# main.net
KiCad netlist of a schematic drawn in EAGLE
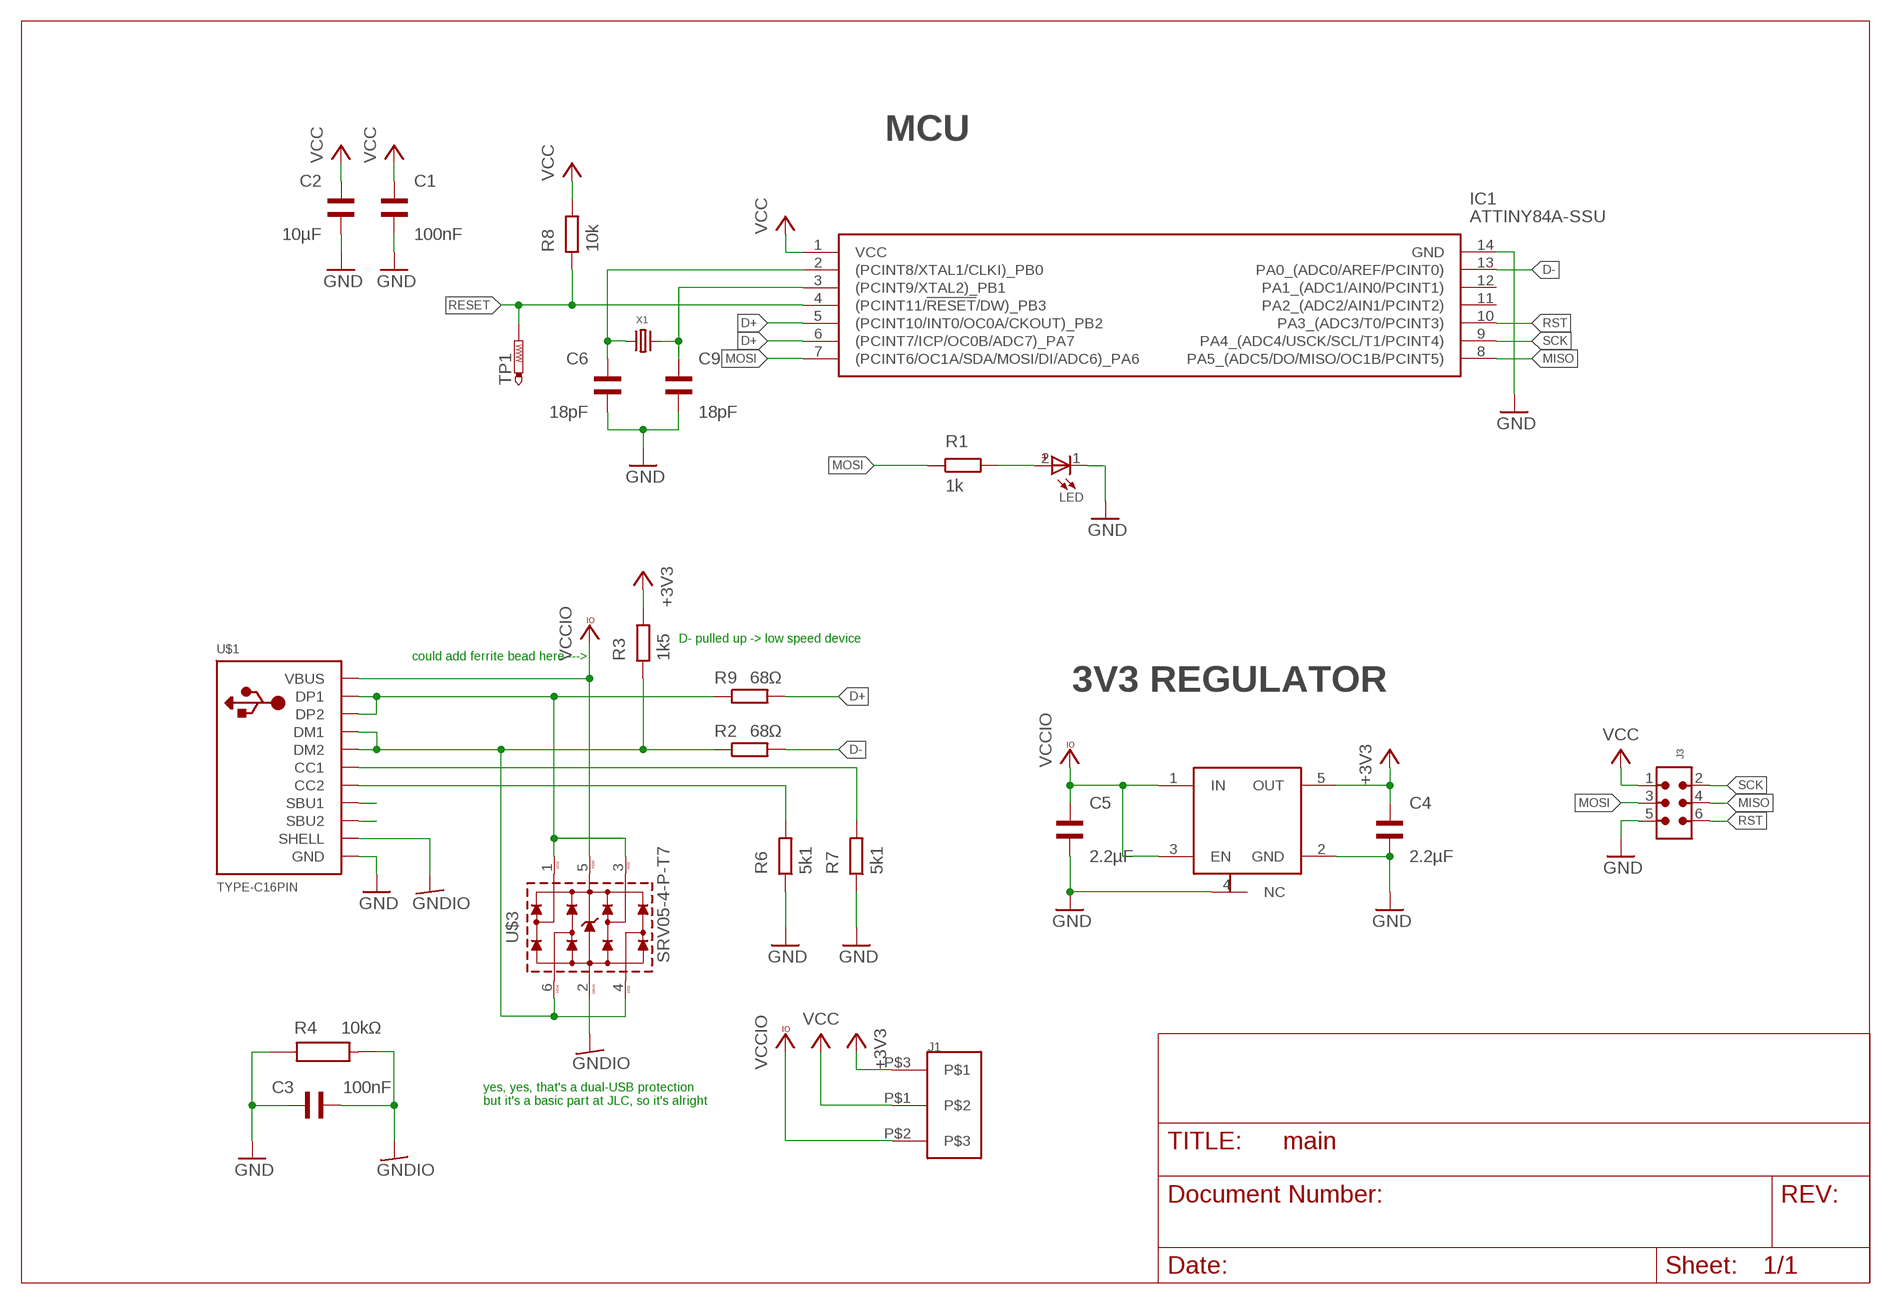
[diagram p0: schematic, sheet 1]

(export (version "E")
  (design (tool "Eeschema 10.0.6"))
  (components
    (comp (ref "C1")
      (value "100nF")
      (footprint "eagle-import:WCAP-CSGP_0603_REFLOW")
      (libsource (lib "eagle-import") (part "WCAP-CSGP_0603_REFLOW_885012206046"))
    )
    (comp (ref "C2")
      (value "10µF")
      (footprint "eagle-import:WCAP-CSGP_0603_REFLOW")
      (libsource (lib "eagle-import") (part "WCAP-CSGP_0603_REFLOW_885012106012"))
    )
    (comp (ref "C3")
      (value "100nF")
      (footprint "eagle-import:WCAP-CSGP_0603_REFLOW")
      (libsource (lib "eagle-import") (part "WCAP-CSGP_0603_REFLOW_885012206046"))
    )
    (comp (ref "C4")
      (value "2.2µF")
      (footprint "eagle-import:WCAP-CSGP_0603_REFLOW")
      (libsource (lib "eagle-import") (part "WCAP-CSGP_0603_REFLOW_885012206027"))
    )
    (comp (ref "C5")
      (value "2.2µF")
      (footprint "eagle-import:WCAP-CSGP_0603_REFLOW")
      (libsource (lib "eagle-import") (part "WCAP-CSGP_0603_REFLOW_885012206027"))
    )
    (comp (ref "C6")
      (value "18pF")
      (footprint "eagle-import:WCAP-CSGP_0603_REFLOW")
      (libsource (lib "eagle-import") (part "WCAP-CSGP_0603_REFLOW_885012206046"))
    )
    (comp (ref "C9")
      (value "18pF")
      (footprint "eagle-import:WCAP-CSGP_0603_REFLOW")
      (libsource (lib "eagle-import") (part "WCAP-CSGP_0603_REFLOW_885012206046"))
    )
    (comp (ref "IC1")
      (value "ATTINY84A-SSU")
      (footprint "eagle-import:SOIC127P600X175-14N")
      (fields (field (name "MOUSER_PART_NUMBER") "556-ATTINY84A-SSU"))
      (libsource (lib "eagle-import") (part "ATTINY84A-SSU"))
    )
    (comp (ref "J1")
      (value "JUMPER1.27")
      (footprint "eagle-import:1.27_JUMPER")
      (libsource (lib "eagle-import") (part "JUMPER1.27"))
    )
    (comp (ref "J3")
      (value "6120XX21621_61200621621")
      (footprint "eagle-import:61200621621")
      (libsource (lib "eagle-import") (part "6120XX21621_61200621621"))
    )
    (comp (ref "LED")
      (value "WL-SMCW_0603_150060GS75000")
      (footprint "eagle-import:WL-SMCW_0603")
      (libsource (lib "eagle-import") (part "WL-SMCW_0603_150060GS75000"))
    )
    (comp (ref "R1")
      (value "1k")
      (footprint "eagle-import:WRIS-KSKE_0402")
      (libsource (lib "eagle-import") (part "RESISTOR_0402"))
    )
    (comp (ref "R2")
      (value "68Ω")
      (footprint "eagle-import:WRIS-KSKE_0402")
      (libsource (lib "eagle-import") (part "RESISTOR_0402"))
    )
    (comp (ref "R3")
      (value "1k5")
      (footprint "eagle-import:WRIS-KSKE_0402")
      (libsource (lib "eagle-import") (part "RESISTOR_0402"))
    )
    (comp (ref "R4")
      (value "10kΩ")
      (footprint "eagle-import:WRIS-PSMB_0603_1.6X0.8X0.35X0.6(LXWXHXPW)")
      (libsource (lib "eagle-import") (part "WRIS-PSMB_0603_1.6X0.8X0.35X0.6_580060716001"))
    )
    (comp (ref "R6")
      (value "5k1")
      (footprint "eagle-import:WRIS-KSKE_0402")
      (libsource (lib "eagle-import") (part "RESISTOR_0402"))
    )
    (comp (ref "R7")
      (value "5k1")
      (footprint "eagle-import:WRIS-KSKE_0402")
      (libsource (lib "eagle-import") (part "RESISTOR_0402"))
    )
    (comp (ref "R8")
      (value "10k")
      (footprint "eagle-import:WRIS-KSKE_0402")
      (libsource (lib "eagle-import") (part "RESISTOR_0402"))
    )
    (comp (ref "R9")
      (value "68Ω")
      (footprint "eagle-import:WRIS-KSKE_0402")
      (libsource (lib "eagle-import") (part "RESISTOR_0402"))
    )
    (comp (ref "TP1")
      (value "PTR1B1,27")
      (footprint "eagle-import:B1,27")
      (libsource (lib "eagle-import") (part "PTR1B1,27"))
    )
    (comp (ref "U$1")
      (value "TYPE-C16PIN")
      (footprint "eagle-import:TYPE-C16PIN")
      (libsource (lib "eagle-import") (part "TYPE-C16PIN"))
    )
    (comp (ref "U$2")
      (value "TLV75533PDBVRSOT-23-5")
      (footprint "eagle-import:DBV_R-PDSO-G5")
      (libsource (lib "eagle-import") (part "TLV75533PDBVRSOT-23-5"))
    )
    (comp (ref "U$3")
      (value "SRV05-4-P-T7")
      (footprint "eagle-import:SOT23-6")
      (libsource (lib "eagle-import") (part "SRV05-4-P-T7"))
    )
    (comp (ref "X1")
      (value "KMD160001210")
      (footprint "eagle-import:M-49USSMD")
      (libsource (lib "eagle-import") (part "KMD160001210"))
    )
  )
  (nets
    (net (code "1") (name "+3V3") (class "Default")
      (node (ref "C4") (pin "2") (pinfunction "2_2") (pintype "passive"))
      (node (ref "J1") (pin "P$3") (pinfunction "P$1_P$3") (pintype "bidirectional"))
      (node (ref "R3") (pin "2") (pinfunction "2_2") (pintype "passive"))
      (node (ref "U$2") (pin "5") (pinfunction "OUT_5") (pintype "bidirectional"))
    )
    (net (code "2") (name "D+") (class "Default")
      (node (ref "IC1") (pin "5") (pinfunction "(PCINT10/INT0/OC0A/CKOUT)_PB2_5") (pintype "bidirectional"))
      (node (ref "IC1") (pin "6") (pinfunction "(PCINT7/ICP/OC0B/ADC7)_PA7_6") (pintype "bidirectional"))
      (node (ref "R9") (pin "2") (pinfunction "2_2") (pintype "passive"))
    )
    (net (code "3") (name "D-") (class "Default")
      (node (ref "IC1") (pin "13") (pinfunction "PA0_(ADC0/AREF/PCINT0)_13") (pintype "bidirectional"))
      (node (ref "R2") (pin "2") (pinfunction "2_2") (pintype "passive"))
    )
    (net (code "4") (name "GND") (class "Default")
      (node (ref "C1") (pin "1") (pinfunction "1_1") (pintype "passive"))
      (node (ref "C2") (pin "1") (pinfunction "1_1") (pintype "passive"))
      (node (ref "C3") (pin "2") (pinfunction "2_2") (pintype "passive"))
      (node (ref "C4") (pin "1") (pinfunction "1_1") (pintype "passive"))
      (node (ref "C5") (pin "1") (pinfunction "1_1") (pintype "passive"))
      (node (ref "C6") (pin "1") (pinfunction "1_1") (pintype "passive"))
      (node (ref "C9") (pin "1") (pinfunction "1_1") (pintype "passive"))
      (node (ref "IC1") (pin "14") (pinfunction "GND_14") (pintype "bidirectional"))
      (node (ref "J3") (pin "5") (pinfunction "5_5") (pintype "passive"))
      (node (ref "LED") (pin "1") (pinfunction "-_1") (pintype "passive"))
      (node (ref "R4") (pin "1") (pinfunction "1_1") (pintype "passive"))
      (node (ref "R6") (pin "1") (pinfunction "1_1") (pintype "passive"))
      (node (ref "R7") (pin "1") (pinfunction "1_1") (pintype "passive"))
      (node (ref "U$1") (pin "A1B12") (pinfunction "GND_A1B12") (pintype "power_in"))
      (node (ref "U$1") (pin "B1A12") (pinfunction "GND_B1A12") (pintype "power_in"))
      (node (ref "U$2") (pin "2") (pinfunction "GND_2") (pintype "bidirectional"))
      (node (ref "U$2") (pin "4") (pinfunction "NC_4") (pintype "bidirectional"))
    )
    (net (code "5") (name "GNDIO") (class "Default")
      (node (ref "C3") (pin "1") (pinfunction "1_1") (pintype "passive"))
      (node (ref "R4") (pin "2") (pinfunction "2_2") (pintype "passive"))
      (node (ref "U$1") (pin "SHELL1") (pinfunction "SHELL_SHELL1") (pintype "bidirectional"))
      (node (ref "U$1") (pin "SHELL2") (pinfunction "SHELL_SHELL2") (pintype "bidirectional"))
      (node (ref "U$1") (pin "SHELL3") (pinfunction "SHELL_SHELL3") (pintype "bidirectional"))
      (node (ref "U$1") (pin "SHELL4") (pinfunction "SHELL_SHELL4") (pintype "bidirectional"))
      (node (ref "U$3") (pin "2") (pinfunction "GND_2") (pintype "passive"))
    )
    (net (code "6") (name "MISO") (class "Default")
      (node (ref "IC1") (pin "8") (pinfunction "PA5_(ADC5/DO/MISO/OC1B/PCINT5)_8") (pintype "bidirectional"))
      (node (ref "J3") (pin "4") (pinfunction "4_4") (pintype "passive"))
    )
    (net (code "7") (name "MOSI") (class "Default")
      (node (ref "IC1") (pin "7") (pinfunction "(PCINT6/OC1A/SDA/MOSI/DI/ADC6)_PA6_7") (pintype "bidirectional"))
      (node (ref "J3") (pin "3") (pinfunction "3_3") (pintype "passive"))
      (node (ref "R1") (pin "1") (pinfunction "1_1") (pintype "passive"))
    )
    (net (code "8") (name "Net-(IC1-(PCINT8{slash}XTAL1{slash}CLKI)_PB0)") (class "Default")
      (node (ref "C6") (pin "2") (pinfunction "2_2") (pintype "passive"))
      (node (ref "IC1") (pin "2") (pinfunction "(PCINT8/XTAL1/CLKI)_PB0_2") (pintype "bidirectional"))
      (node (ref "X1") (pin "P$1") (pinfunction "1_P$1") (pintype "passive"))
    )
    (net (code "9") (name "Net-(IC1-(PCINT9{slash}XTAL2)_PB1)") (class "Default")
      (node (ref "C9") (pin "2") (pinfunction "2_2") (pintype "passive"))
      (node (ref "IC1") (pin "3") (pinfunction "(PCINT9/XTAL2)_PB1_3") (pintype "bidirectional"))
      (node (ref "X1") (pin "P$2") (pinfunction "2_P$2") (pintype "passive"))
    )
    (net (code "10") (name "Net-(LED-+)") (class "Default")
      (node (ref "LED") (pin "2") (pinfunction "+_2") (pintype "passive"))
      (node (ref "R1") (pin "2") (pinfunction "2_2") (pintype "passive"))
    )
    (net (code "11") (name "Net-(U$1-CC1)") (class "Default")
      (node (ref "R7") (pin "2") (pinfunction "2_2") (pintype "passive"))
      (node (ref "U$1") (pin "A5") (pinfunction "CC1_A5") (pintype "bidirectional"))
    )
    (net (code "12") (name "Net-(U$1-CC2)") (class "Default")
      (node (ref "R6") (pin "2") (pinfunction "2_2") (pintype "passive"))
      (node (ref "U$1") (pin "B5") (pinfunction "CC2_B5") (pintype "bidirectional"))
    )
    (net (code "13") (name "Net-(U$1-DM1)") (class "Default")
      (node (ref "R2") (pin "1") (pinfunction "1_1") (pintype "passive"))
      (node (ref "R3") (pin "1") (pinfunction "1_1") (pintype "passive"))
      (node (ref "U$1") (pin "A7") (pinfunction "DM1_A7") (pintype "bidirectional"))
      (node (ref "U$1") (pin "B7") (pinfunction "DM2_B7") (pintype "bidirectional"))
      (node (ref "U$3") (pin "4") (pinfunction "IO3_4") (pintype "passive"))
      (node (ref "U$3") (pin "6") (pinfunction "IO4_6") (pintype "passive"))
    )
    (net (code "14") (name "Net-(U$1-DP1)") (class "Default")
      (node (ref "R9") (pin "1") (pinfunction "1_1") (pintype "passive"))
      (node (ref "U$1") (pin "A6") (pinfunction "DP1_A6") (pintype "bidirectional"))
      (node (ref "U$1") (pin "B6") (pinfunction "DP2_B6") (pintype "bidirectional"))
      (node (ref "U$3") (pin "1") (pinfunction "IO1_1") (pintype "passive"))
      (node (ref "U$3") (pin "3") (pinfunction "IO2_3") (pintype "passive"))
    )
    (net (code "15") (name "RESET") (class "Default")
      (node (ref "IC1") (pin "4") (pinfunction "(PCINT11/~{RESET}/DW)_PB3_4") (pintype "bidirectional"))
      (node (ref "R8") (pin "1") (pinfunction "1_1") (pintype "passive"))
      (node (ref "TP1") (pin "TP") (pinfunction "TP_TP") (pintype "input"))
    )
    (net (code "16") (name "RST") (class "Default")
      (node (ref "IC1") (pin "10") (pinfunction "PA3_(ADC3/T0/PCINT3)_10") (pintype "bidirectional"))
      (node (ref "J3") (pin "6") (pinfunction "6_6") (pintype "passive"))
    )
    (net (code "17") (name "SCK") (class "Default")
      (node (ref "IC1") (pin "9") (pinfunction "PA4_(ADC4/USCK/SCL/T1/PCINT4)_9") (pintype "bidirectional"))
      (node (ref "J3") (pin "2") (pinfunction "2_2") (pintype "passive"))
    )
    (net (code "18") (name "VCC") (class "Default")
      (node (ref "C1") (pin "2") (pinfunction "2_2") (pintype "passive"))
      (node (ref "C2") (pin "2") (pinfunction "2_2") (pintype "passive"))
      (node (ref "IC1") (pin "1") (pinfunction "VCC_1") (pintype "bidirectional"))
      (node (ref "J1") (pin "P$1") (pinfunction "P$2_P$1") (pintype "bidirectional"))
      (node (ref "J3") (pin "1") (pinfunction "1_1") (pintype "passive"))
      (node (ref "R8") (pin "2") (pinfunction "2_2") (pintype "passive"))
    )
    (net (code "19") (name "VCCIO") (class "Default")
      (node (ref "C5") (pin "2") (pinfunction "2_2") (pintype "passive"))
      (node (ref "J1") (pin "P$2") (pinfunction "P$3_P$2") (pintype "bidirectional"))
      (node (ref "U$1") (pin "A4B9") (pinfunction "VBUS_A4B9") (pintype "power_in"))
      (node (ref "U$1") (pin "B4A9") (pinfunction "VBUS_B4A9") (pintype "power_in"))
      (node (ref "U$2") (pin "1") (pinfunction "IN_1") (pintype "bidirectional"))
      (node (ref "U$2") (pin "3") (pinfunction "EN_3") (pintype "bidirectional"))
      (node (ref "U$3") (pin "5") (pinfunction "VDD_5") (pintype "passive"))
    )
    (net (code "20") (name "unconnected-(IC1-PA1_(ADC1{slash}AIN0{slash}PCINT1)-Pad12)") (class "Default")
      (node (ref "IC1") (pin "12") (pinfunction "PA1_(ADC1/AIN0/PCINT1)_12") (pintype "bidirectional"))
    )
    (net (code "21") (name "unconnected-(IC1-PA2_(ADC2{slash}AIN1{slash}PCINT2)-Pad11)") (class "Default")
      (node (ref "IC1") (pin "11") (pinfunction "PA2_(ADC2/AIN1/PCINT2)_11") (pintype "bidirectional"))
    )
    (net (code "22") (name "unconnected-(U$1-SBU1-PadA8)") (class "Default")
      (node (ref "U$1") (pin "A8") (pinfunction "SBU1_A8") (pintype "power_in"))
    )
    (net (code "23") (name "unconnected-(U$1-SBU2-PadB8)") (class "Default")
      (node (ref "U$1") (pin "B8") (pinfunction "SBU2_B8") (pintype "power_in"))
    )
  )
)
